# atxmega.net
KiCad netlist of a schematic drawn in Altium Designer
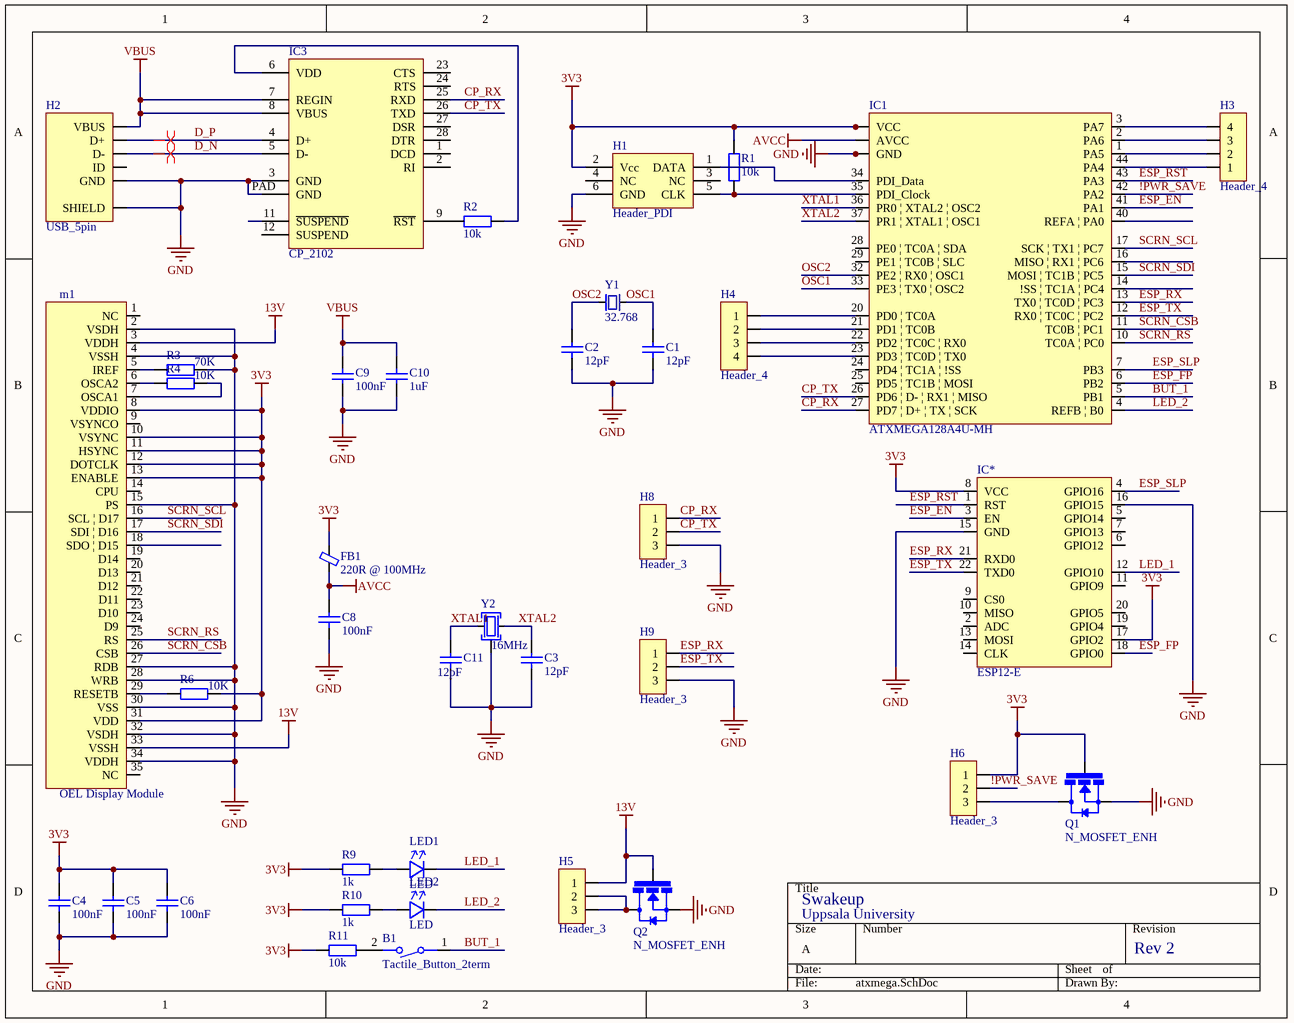
[diagram p0: atxmega.SchDoc]

(export (version "E")
  (design (tool "Eeschema 10.0.6"))
  (components
    (comp (ref "B1")
      (value "Tactile_Button_2term")
      (footprint "TACTILE_MINATUE_SMD_3.5x6mm")
      (libsource (lib "AranCustomFootprints") (part "Tactile_Button_2term"))
    )
    (comp (ref "C1")
      (value "12pF")
      (footprint "C0402")
      (description "Schematic symbol of a capacitor")
      (libsource (lib "AranCustomFootprints") (part "Capacitor"))
    )
    (comp (ref "C2")
      (value "12pF")
      (footprint "C0402")
      (description "Schematic symbol of a capacitor")
      (libsource (lib "AranCustomFootprints") (part "Capacitor"))
    )
    (comp (ref "C3")
      (value "12pF")
      (footprint "C0402")
      (description "Schematic symbol of a capacitor")
      (libsource (lib "AranCustomFootprints") (part "Capacitor"))
    )
    (comp (ref "C4")
      (value "100nF")
      (footprint "C0603")
      (description "Schematic symbol of a capacitor")
      (libsource (lib "AranCustomFootprints") (part "Capacitor"))
    )
    (comp (ref "C5")
      (value "100nF")
      (footprint "C0603")
      (description "Schematic symbol of a capacitor")
      (libsource (lib "AranCustomFootprints") (part "Capacitor"))
    )
    (comp (ref "C6")
      (value "100nF")
      (footprint "C0603")
      (description "Schematic symbol of a capacitor")
      (libsource (lib "AranCustomFootprints") (part "Capacitor"))
    )
    (comp (ref "C8")
      (value "100nF")
      (footprint "C0603")
      (description "Schematic symbol of a capacitor")
      (libsource (lib "AranCustomFootprints") (part "Capacitor"))
    )
    (comp (ref "C9")
      (value "100nF")
      (footprint "C0603")
      (description "Schematic symbol of a capacitor")
      (libsource (lib "AranCustomFootprints") (part "Capacitor"))
    )
    (comp (ref "C10")
      (value "1uF")
      (footprint "C0603")
      (description "Schematic symbol of a capacitor")
      (libsource (lib "AranCustomFootprints") (part "Capacitor"))
    )
    (comp (ref "C11")
      (value "12pF")
      (footprint "C0402")
      (description "Schematic symbol of a capacitor")
      (libsource (lib "AranCustomFootprints") (part "Capacitor"))
    )
    (comp (ref "FB1")
      (value "220R @ 100MHz")
      (footprint "L0805")
      (libsource (lib "AranCustomFootprints") (part "Ferrite"))
    )
    (comp (ref "H1")
      (value "Header_PDI")
      (footprint "6-HEADER_BOXED")
      (description "6-pin Boxed header with pinout used for PDI programming by Atmel programmers")
      (libsource (lib "AranCustomFootprints") (part "Header_PDI"))
    )
    (comp (ref "H2")
      (value "USB_5pin")
      (footprint "USB_Micro_B_RECEPTABLE_FCI")
      (description "5 Pins USB Connector")
      (libsource (lib "AranCustomFootprints") (part "USB_5pin"))
    )
    (comp (ref "H3")
      (value "Header_4")
      (footprint "Header_MALE_4")
      (description "Generic 4pin header symbol")
      (libsource (lib "AranCustomFootprints") (part "Header_4"))
    )
    (comp (ref "H4")
      (value "Header_4")
      (footprint "Header_MALE_4")
      (description "Generic 4pin header symbol")
      (libsource (lib "") (part "Header_4_1"))
    )
    (comp (ref "H5")
      (value "Header_3")
      (footprint "Header_MALE_3")
      (description "Generic 3pin header symbol")
      (libsource (lib "AranCustomFootprints") (part "Header_3"))
    )
    (comp (ref "H6")
      (value "Header_3")
      (footprint "Header_MALE_3")
      (description "Generic 3pin header symbol")
      (libsource (lib "AranCustomFootprints") (part "Header_3"))
    )
    (comp (ref "H8")
      (value "Header_3")
      (footprint "Header_MALE_3")
      (description "Generic 3pin header symbol")
      (libsource (lib "AranCustomFootprints") (part "Header_3"))
    )
    (comp (ref "H9")
      (value "Header_3")
      (footprint "Header_MALE_3")
      (description "Generic 3pin header symbol")
      (libsource (lib "AranCustomFootprints") (part "Header_3"))
    )
    (comp (ref "IC*") (value "ESP12-E") (footprint "ESP12-E") (libsource (lib "elmarlib") (part "ESP12-E")))
    (comp (ref "IC1")
      (value "ATXMEGA128A4U-MH")
      (footprint "44-VFQFN-E")
      (description "AVR AVR® XMEGA® A4U Microcontroller IC 8/16-Bit 32MHz 128KB (64K x 16) FLASH 44-VQFN (7x7)")
      (libsource (lib "elmarlib") (part "ATXMEGA128A4U-MH"))
    )
    (comp (ref "IC3")
      (value "CP_2102")
      (footprint "28-QFN_Exposed_pad")
      (description "Single chip USB to UART Bridge")
      (libsource (lib "AranCustomFootprints") (part "CP_2102"))
    )
    (comp (ref "LED1")
      (value "LED")
      (footprint "0603_LED")
      (description "Schematic symbol of a LED")
      (libsource (lib "AranCustomFootprints") (part "LED"))
    )
    (comp (ref "LED2")
      (value "LED")
      (footprint "0603_LED")
      (description "Schematic symbol of a LED")
      (libsource (lib "AranCustomFootprints") (part "LED"))
    )
    (comp (ref "m1")
      (value "OEL Display Module")
      (footprint "FFC-35-pin-0.5")
      (description "Part ID: UG-6028GDEAF01")
      (libsource (lib "elmarlib") (part "OEL Display Module"))
    )
    (comp (ref "Q1")
      (value "N_MOSFET_ENH")
      (footprint "SOT-23")
      (description "N Channel Enhancement type MOSFET schematic symbol")
      (libsource (lib "AranCustomFootprints") (part "N_MOSFET_ENH"))
    )
    (comp (ref "Q2")
      (value "N_MOSFET_ENH")
      (footprint "SOT-23")
      (description "N Channel Enhancement type MOSFET schematic symbol")
      (libsource (lib "AranCustomFootprints") (part "N_MOSFET_ENH"))
    )
    (comp (ref "R1")
      (value "10k")
      (footprint "R0603")
      (description "Schematic symbol of a resistor")
      (libsource (lib "AranCustomFootprints") (part "Resistor"))
    )
    (comp (ref "R2")
      (value "10k")
      (footprint "R0603")
      (description "Schematic symbol of a resistor")
      (libsource (lib "AranCustomFootprints") (part "Resistor"))
    )
    (comp (ref "R3")
      (value "70K")
      (footprint "R0603")
      (description "Schematic symbol of a resistor")
      (libsource (lib "AranCustomFootprints") (part "Resistor"))
    )
    (comp (ref "R4")
      (value "10K")
      (footprint "R0603")
      (description "Schematic symbol of a resistor")
      (libsource (lib "AranCustomFootprints") (part "Resistor"))
    )
    (comp (ref "R6")
      (value "10K")
      (footprint "R0603")
      (description "Schematic symbol of a resistor")
      (libsource (lib "AranCustomFootprints") (part "Resistor"))
    )
    (comp (ref "R9")
      (value "1k")
      (footprint "R0603")
      (description "Schematic symbol of a resistor")
      (libsource (lib "AranCustomFootprints") (part "Resistor"))
    )
    (comp (ref "R10")
      (value "1k")
      (footprint "R0603")
      (description "Schematic symbol of a resistor")
      (libsource (lib "AranCustomFootprints") (part "Resistor"))
    )
    (comp (ref "R11")
      (value "10k")
      (footprint "R0603")
      (description "Schematic symbol of a resistor")
      (libsource (lib "AranCustomFootprints") (part "Resistor"))
    )
    (comp (ref "Y1")
      (value "32.768")
      (footprint "crystal_6.2x2.1x2.1")
      (description "32.768kHz ±20ppm Crystal 12.5pF 35 kOhm -10°C ~ 60°C Through Hole Cylindrical Can, Radial")
      (libsource (lib "elmarlib") (part "Abracon LLC AB26T-32.768KHZ"))
    )
    (comp (ref "Y2")
      (value "16MHz")
      (footprint "Crystal_3.2x2.5")
      (description "Schematic symbol of a 2pin crystal with case connection")
      (libsource (lib "AranCustomFootprints") (part "Crystal_Ground"))
    )
  )
  (nets
    (net (code "1") (name "/!PWR_SAVE") (class "Default")
      (node (ref "H6") (pin "2") (pinfunction "2_2") (pintype "passive"))
      (node (ref "IC1") (pin "42") (pinfunction "PA2_42") (pintype "passive"))
    )
    (net (code "2") (name "/BUT_1") (class "Default")
      (node (ref "B1") (pin "1") (pintype "passive"))
      (node (ref "IC1") (pin "5") (pinfunction "PB1_5") (pintype "passive"))
    )
    (net (code "3") (name "/CP_RX") (class "Default")
      (node (ref "H8") (pin "1") (pinfunction "1_1") (pintype "passive"))
      (node (ref "IC1") (pin "27") (pinfunction "PD7_¦_D+_¦_TX_¦_SCK_27") (pintype "passive"))
      (node (ref "IC3") (pin "25") (pinfunction "RXD_25") (pintype "passive"))
    )
    (net (code "4") (name "/CP_TX") (class "Default")
      (node (ref "H8") (pin "2") (pinfunction "2_2") (pintype "passive"))
      (node (ref "IC1") (pin "26") (pinfunction "PD6_¦_D-_¦_RX1_¦_MISO_26") (pintype "passive"))
      (node (ref "IC3") (pin "26") (pinfunction "TXD_26") (pintype "passive"))
    )
    (net (code "5") (name "/D_N") (class "Default")
      (node (ref "H2") (pin "2") (pinfunction "D-_2") (pintype "passive"))
      (node (ref "IC3") (pin "5") (pinfunction "D-_5") (pintype "passive"))
    )
    (net (code "6") (name "/D_P") (class "Default")
      (node (ref "H2") (pin "3") (pinfunction "D+_3") (pintype "passive"))
      (node (ref "IC3") (pin "4") (pinfunction "D+_4") (pintype "passive"))
    )
    (net (code "7") (name "/ESP_EN") (class "Default")
      (node (ref "IC*") (pin "3") (pinfunction "EN_3") (pintype "passive"))
      (node (ref "IC1") (pin "41") (pinfunction "PA1_41") (pintype "passive"))
    )
    (net (code "8") (name "/ESP_FP") (class "Default")
      (node (ref "IC*") (pin "18") (pinfunction "GPIO0_18") (pintype "passive"))
      (node (ref "IC1") (pin "6") (pinfunction "PB2_6") (pintype "passive"))
    )
    (net (code "9") (name "/ESP_RST") (class "Default")
      (node (ref "IC*") (pin "1") (pinfunction "RST_1") (pintype "passive"))
      (node (ref "IC1") (pin "43") (pinfunction "PA3_43") (pintype "passive"))
    )
    (net (code "10") (name "/ESP_RX") (class "Default")
      (node (ref "H9") (pin "1") (pinfunction "1_1") (pintype "passive"))
      (node (ref "IC*") (pin "21") (pinfunction "RXD0_21") (pintype "passive"))
      (node (ref "IC1") (pin "13") (pinfunction "TX0_¦_TC0D_¦_PC3_13") (pintype "passive"))
    )
    (net (code "11") (name "/ESP_SLP") (class "Default")
      (node (ref "IC*") (pin "4") (pinfunction "GPIO16_4") (pintype "passive"))
      (node (ref "IC1") (pin "7") (pinfunction "PB3_7") (pintype "passive"))
    )
    (net (code "12") (name "/ESP_TX") (class "Default")
      (node (ref "H9") (pin "2") (pinfunction "2_2") (pintype "passive"))
      (node (ref "IC*") (pin "22") (pinfunction "TXD0_22") (pintype "passive"))
      (node (ref "IC1") (pin "12") (pinfunction "RX0_¦_TC0C_¦_PC2_12") (pintype "passive"))
    )
    (net (code "13") (name "/LED_1") (class "Default")
      (node (ref "IC*") (pin "12") (pinfunction "GPIO10_12") (pintype "passive"))
      (node (ref "LED1") (pin "C") (pinfunction "Cathode_C") (pintype "passive"))
    )
    (net (code "14") (name "/LED_2") (class "Default")
      (node (ref "IC1") (pin "4") (pinfunction "REFB_¦_B0_4") (pintype "passive"))
      (node (ref "LED2") (pin "C") (pinfunction "Cathode_C") (pintype "passive"))
    )
    (net (code "15") (name "/OSC1") (class "Default")
      (node (ref "C1") (pin "1") (pinfunction "1_1") (pintype "passive"))
      (node (ref "IC1") (pin "33") (pinfunction "PE3_¦_TX0_¦_OSC2_33") (pintype "passive"))
      (node (ref "Y1") (pin "0") (pinfunction "XTAL2_0") (pintype "passive"))
    )
    (net (code "16") (name "/OSC2") (class "Default")
      (node (ref "C2") (pin "1") (pinfunction "1_1") (pintype "passive"))
      (node (ref "IC1") (pin "32") (pinfunction "PE2_¦_RX0_¦_OSC1_32") (pintype "passive"))
      (node (ref "Y1") (pin "1") (pinfunction "XTAL1_1") (pintype "passive"))
    )
    (net (code "17") (name "/SCRN_CSB") (class "Default")
      (node (ref "IC1") (pin "11") (pinfunction "TC0B_¦_PC1_11") (pintype "passive"))
      (node (ref "m1") (pin "26") (pinfunction "CSB_26") (pintype "passive"))
    )
    (net (code "18") (name "/SCRN_RS") (class "Default")
      (node (ref "IC1") (pin "10") (pinfunction "TC0A_¦_PC0_10") (pintype "passive"))
      (node (ref "m1") (pin "25") (pinfunction "RS_25") (pintype "passive"))
    )
    (net (code "19") (name "/SCRN_SCL") (class "Default")
      (node (ref "IC1") (pin "17") (pinfunction "SCK_¦_TX1_¦_PC7_17") (pintype "passive"))
      (node (ref "m1") (pin "16") (pinfunction "SCL_¦_D17_16") (pintype "passive"))
    )
    (net (code "20") (name "/SCRN_SDI") (class "Default")
      (node (ref "IC1") (pin "15") (pinfunction "MOSI_¦_TC1B_¦_PC5_15") (pintype "passive"))
      (node (ref "m1") (pin "17") (pinfunction "SDI_¦_D16_17") (pintype "passive"))
    )
    (net (code "21") (name "/XTAL1") (class "Default")
      (node (ref "C11") (pin "1") (pinfunction "1_1") (pintype "passive"))
      (node (ref "IC1") (pin "36") (pinfunction "PR0_¦_XTAL2_¦_OSC2_36") (pintype "passive"))
      (node (ref "Y2") (pin "1") (pinfunction "1_1") (pintype "passive"))
    )
    (net (code "22") (name "/XTAL2") (class "Default")
      (node (ref "C3") (pin "1") (pinfunction "1_1") (pintype "passive"))
      (node (ref "IC1") (pin "37") (pinfunction "PR1_¦_XTAL1_¦_OSC1_37") (pintype "passive"))
      (node (ref "Y2") (pin "3") (pinfunction "3_3") (pintype "passive"))
    )
    (net (code "23") (name "3V3") (class "Default")
      (node (ref "C4") (pin "1") (pinfunction "1_1") (pintype "passive"))
      (node (ref "C5") (pin "1") (pinfunction "1_1") (pintype "passive"))
      (node (ref "C6") (pin "1") (pinfunction "1_1") (pintype "passive"))
      (node (ref "FB1") (pin "2") (pinfunction "2_2") (pintype "passive"))
      (node (ref "H1") (pin "2") (pinfunction "Vcc_2") (pintype "passive"))
      (node (ref "H6") (pin "1") (pinfunction "1_1") (pintype "passive"))
      (node (ref "IC*") (pin "17") (pinfunction "GPIO2_17") (pintype "passive"))
      (node (ref "IC*") (pin "8") (pinfunction "VCC_8") (pintype "passive"))
      (node (ref "IC1") (pin "19") (pinfunction "VCC_19") (pintype "passive"))
      (node (ref "IC1") (pin "31") (pinfunction "VCC_31") (pintype "passive"))
      (node (ref "IC1") (pin "9") (pinfunction "VCC_9") (pintype "passive"))
      (node (ref "Q1") (pin "1") (pinfunction "Gate_1") (pintype "passive"))
      (node (ref "R1") (pin "1") (pinfunction "1_1") (pintype "passive"))
      (node (ref "R10") (pin "1") (pinfunction "1_1") (pintype "passive"))
      (node (ref "R11") (pin "1") (pinfunction "1_1") (pintype "passive"))
      (node (ref "R6") (pin "1") (pinfunction "1_1") (pintype "passive"))
      (node (ref "R9") (pin "1") (pinfunction "1_1") (pintype "passive"))
      (node (ref "m1") (pin "10") (pinfunction "VSYNC_10") (pintype "passive"))
      (node (ref "m1") (pin "11") (pinfunction "HSYNC_11") (pintype "passive"))
      (node (ref "m1") (pin "12") (pinfunction "DOTCLK_12") (pintype "passive"))
      (node (ref "m1") (pin "13") (pinfunction "ENABLE_13") (pintype "passive"))
      (node (ref "m1") (pin "31") (pinfunction "VDD_31") (pintype "passive"))
      (node (ref "m1") (pin "8") (pinfunction "VDDIO_8") (pintype "passive"))
    )
    (net (code "24") (name "13V") (class "Default")
      (node (ref "H5") (pin "1") (pinfunction "1_1") (pintype "passive"))
      (node (ref "Q2") (pin "1") (pinfunction "Gate_1") (pintype "passive"))
      (node (ref "m1") (pin "3") (pinfunction "VDDH_3") (pintype "passive"))
      (node (ref "m1") (pin "33") (pinfunction "VSSH_33") (pintype "passive"))
    )
    (net (code "25") (name "AVCC") (class "Default")
      (node (ref "C8") (pin "1") (pinfunction "1_1") (pintype "passive"))
      (node (ref "FB1") (pin "1") (pinfunction "1_1") (pintype "passive"))
      (node (ref "IC1") (pin "39") (pinfunction "AVCC_39") (pintype "passive"))
    )
    (net (code "26") (name "GND") (class "Default")
      (node (ref "C1") (pin "2") (pinfunction "2_2") (pintype "passive"))
      (node (ref "C10") (pin "1") (pinfunction "1_1") (pintype "passive"))
      (node (ref "C11") (pin "2") (pinfunction "2_2") (pintype "passive"))
      (node (ref "C2") (pin "2") (pinfunction "2_2") (pintype "passive"))
      (node (ref "C3") (pin "2") (pinfunction "2_2") (pintype "passive"))
      (node (ref "C4") (pin "2") (pinfunction "2_2") (pintype "passive"))
      (node (ref "C5") (pin "2") (pinfunction "2_2") (pintype "passive"))
      (node (ref "C6") (pin "2") (pinfunction "2_2") (pintype "passive"))
      (node (ref "C8") (pin "2") (pinfunction "2_2") (pintype "passive"))
      (node (ref "C9") (pin "1") (pinfunction "1_1") (pintype "passive"))
      (node (ref "H1") (pin "6") (pinfunction "GND_6") (pintype "passive"))
      (node (ref "H2") (pin "5") (pinfunction "GND_5") (pintype "passive"))
      (node (ref "H2") (pin "SHIELD") (pinfunction "SHIELD_SHIELD") (pintype "passive"))
      (node (ref "H8") (pin "3") (pinfunction "3_3") (pintype "passive"))
      (node (ref "H9") (pin "3") (pinfunction "3_3") (pintype "passive"))
      (node (ref "IC*") (pin "15") (pinfunction "GND_15") (pintype "passive"))
      (node (ref "IC*") (pin "16") (pinfunction "GPIO15_16") (pintype "passive"))
      (node (ref "IC1") (pin "18") (pinfunction "GND_18") (pintype "passive"))
      (node (ref "IC1") (pin "30") (pinfunction "GND_30") (pintype "passive"))
      (node (ref "IC1") (pin "38") (pinfunction "GND_38") (pintype "passive"))
      (node (ref "IC1") (pin "45") (pinfunction "GND_45") (pintype "passive"))
      (node (ref "IC1") (pin "8") (pinfunction "GND_8") (pintype "passive"))
      (node (ref "IC3") (pin "3") (pinfunction "GND_3") (pintype "passive"))
      (node (ref "IC3") (pin "PAD") (pinfunction "GND_PAD") (pintype "passive"))
      (node (ref "Q1") (pin "2") (pinfunction "Source_2") (pintype "passive"))
      (node (ref "Q2") (pin "2") (pinfunction "Source_2") (pintype "passive"))
      (node (ref "R3") (pin "1") (pinfunction "1_1") (pintype "passive"))
      (node (ref "Y2") (pin "2") (pinfunction "2_2") (pintype "passive"))
      (node (ref "m1") (pin "15") (pinfunction "PS_15") (pintype "passive"))
      (node (ref "m1") (pin "2") (pinfunction "VSDH_2") (pintype "passive"))
      (node (ref "m1") (pin "27") (pinfunction "RDB_27") (pintype "passive"))
      (node (ref "m1") (pin "28") (pinfunction "WRB_28") (pintype "passive"))
      (node (ref "m1") (pin "30") (pinfunction "VSS_30") (pintype "passive"))
      (node (ref "m1") (pin "32") (pinfunction "VSDH_32") (pintype "passive"))
      (node (ref "m1") (pin "34") (pinfunction "VDDH_34") (pintype "passive"))
      (node (ref "m1") (pin "4") (pinfunction "VSSH_4") (pintype "passive"))
    )
    (net (code "27") (name "Net-(B1-Pad2)") (class "Default")
      (node (ref "B1") (pin "2") (pintype "passive"))
      (node (ref "R11") (pin "2") (pinfunction "2_2") (pintype "passive"))
    )
    (net (code "28") (name "Net-(H1-CLK)") (class "Default")
      (node (ref "H1") (pin "5") (pinfunction "CLK_5") (pintype "passive"))
      (node (ref "IC1") (pin "35") (pinfunction "PDI_Clock_35") (pintype "passive"))
      (node (ref "R1") (pin "2") (pinfunction "2_2") (pintype "passive"))
    )
    (net (code "29") (name "Net-(H1-DATA)") (class "Default")
      (node (ref "H1") (pin "1") (pinfunction "DATA_1") (pintype "passive"))
      (node (ref "IC1") (pin "34") (pinfunction "PDI_Data_34") (pintype "passive"))
    )
    (net (code "30") (name "Net-(IC1-PA4)") (class "Default")
      (node (ref "H3") (pin "1") (pinfunction "1_1") (pintype "passive"))
      (node (ref "IC1") (pin "44") (pinfunction "PA4_44") (pintype "passive"))
    )
    (net (code "31") (name "Net-(IC1-PA5)") (class "Default")
      (node (ref "H3") (pin "2") (pinfunction "2_2") (pintype "passive"))
      (node (ref "IC1") (pin "1") (pinfunction "PA5_1") (pintype "passive"))
    )
    (net (code "32") (name "Net-(IC1-PA6)") (class "Default")
      (node (ref "H3") (pin "3") (pinfunction "3_3") (pintype "passive"))
      (node (ref "IC1") (pin "2") (pinfunction "PA6_2") (pintype "passive"))
    )
    (net (code "33") (name "Net-(IC1-PA7)") (class "Default")
      (node (ref "H3") (pin "4") (pinfunction "4_4") (pintype "passive"))
      (node (ref "IC1") (pin "3") (pinfunction "PA7_3") (pintype "passive"))
    )
    (net (code "34") (name "Net-(IC1-PD0_¦_TC0A)") (class "Default")
      (node (ref "H4") (pin "1") (pinfunction "1_1") (pintype "passive"))
      (node (ref "IC1") (pin "20") (pinfunction "PD0_¦_TC0A_20") (pintype "passive"))
    )
    (net (code "35") (name "Net-(IC1-PD1_¦_TC0B)") (class "Default")
      (node (ref "H4") (pin "2") (pinfunction "2_2") (pintype "passive"))
      (node (ref "IC1") (pin "21") (pinfunction "PD1_¦_TC0B_21") (pintype "passive"))
    )
    (net (code "36") (name "Net-(IC1-PD2_¦_TC0C_¦_RX0)") (class "Default")
      (node (ref "H4") (pin "3") (pinfunction "3_3") (pintype "passive"))
      (node (ref "IC1") (pin "22") (pinfunction "PD2_¦_TC0C_¦_RX0_22") (pintype "passive"))
    )
    (net (code "37") (name "Net-(IC1-PD3_¦_TC0D_¦_TX0)") (class "Default")
      (node (ref "H4") (pin "4") (pinfunction "4_4") (pintype "passive"))
      (node (ref "IC1") (pin "23") (pinfunction "PD3_¦_TC0D_¦_TX0_23") (pintype "passive"))
    )
    (net (code "38") (name "Net-(IC3-VDD)") (class "Default")
      (node (ref "IC3") (pin "6") (pinfunction "VDD_6") (pintype "passive"))
      (node (ref "R2") (pin "1") (pinfunction "1_1") (pintype "passive"))
    )
    (net (code "39") (name "Net-(IC3-~{RST})") (class "Default")
      (node (ref "IC3") (pin "9") (pinfunction "~{RST}_9") (pintype "passive"))
      (node (ref "R2") (pin "2") (pinfunction "2_2") (pintype "passive"))
    )
    (net (code "40") (name "Net-(LED1-Anode)") (class "Default")
      (node (ref "LED1") (pin "A") (pinfunction "Anode_A") (pintype "passive"))
      (node (ref "R9") (pin "2") (pinfunction "2_2") (pintype "passive"))
    )
    (net (code "41") (name "Net-(LED2-Anode)") (class "Default")
      (node (ref "LED2") (pin "A") (pinfunction "Anode_A") (pintype "passive"))
      (node (ref "R10") (pin "2") (pinfunction "2_2") (pintype "passive"))
    )
    (net (code "42") (name "Net-(Q1-Drain)") (class "Default")
      (node (ref "H6") (pin "3") (pinfunction "3_3") (pintype "passive"))
      (node (ref "Q1") (pin "3") (pinfunction "Drain_3") (pintype "passive"))
    )
    (net (code "43") (name "Net-(Q2-Drain)") (class "Default")
      (node (ref "H5") (pin "2") (pinfunction "2_2") (pintype "passive"))
      (node (ref "H5") (pin "3") (pinfunction "3_3") (pintype "passive"))
      (node (ref "Q2") (pin "3") (pinfunction "Drain_3") (pintype "passive"))
    )
    (net (code "44") (name "Net-(m1-IREF)") (class "Default")
      (node (ref "R3") (pin "2") (pinfunction "2_2") (pintype "passive"))
      (node (ref "m1") (pin "5") (pinfunction "IREF_5") (pintype "passive"))
    )
    (net (code "45") (name "Net-(m1-OSCA1)") (class "Default")
      (node (ref "R4") (pin "1") (pinfunction "1_1") (pintype "passive"))
      (node (ref "m1") (pin "7") (pinfunction "OSCA1_7") (pintype "passive"))
    )
    (net (code "46") (name "Net-(m1-OSCA2)") (class "Default")
      (node (ref "R4") (pin "2") (pinfunction "2_2") (pintype "passive"))
      (node (ref "m1") (pin "6") (pinfunction "OSCA2_6") (pintype "passive"))
    )
    (net (code "47") (name "Net-(m1-RESETB)") (class "Default")
      (node (ref "R6") (pin "2") (pinfunction "2_2") (pintype "passive"))
      (node (ref "m1") (pin "29") (pinfunction "RESETB_29") (pintype "passive"))
    )
    (net (code "48") (name "VBUS") (class "Default")
      (node (ref "C10") (pin "2") (pinfunction "2_2") (pintype "passive"))
      (node (ref "C9") (pin "2") (pinfunction "2_2") (pintype "passive"))
      (node (ref "H2") (pin "1") (pinfunction "VBUS_1") (pintype "passive"))
      (node (ref "IC3") (pin "7") (pinfunction "REGIN_7") (pintype "passive"))
      (node (ref "IC3") (pin "8") (pinfunction "VBUS_8") (pintype "passive"))
    )
    (net (code "49") (name "unconnected-(H1-NC-Pad3)") (class "Default")
      (node (ref "H1") (pin "3") (pinfunction "NC_3") (pintype "passive"))
    )
    (net (code "50") (name "unconnected-(H1-NC-Pad4)") (class "Default")
      (node (ref "H1") (pin "4") (pinfunction "NC_4") (pintype "passive"))
    )
    (net (code "51") (name "unconnected-(H2-ID-Pad4)") (class "Default")
      (node (ref "H2") (pin "4") (pinfunction "ID_4") (pintype "passive"))
    )
    (net (code "52") (name "unconnected-(IC*-ADC-Pad2)") (class "Default")
      (node (ref "IC*") (pin "2") (pinfunction "ADC_2") (pintype "passive"))
    )
    (net (code "53") (name "unconnected-(IC*-CLK-Pad14)") (class "Default")
      (node (ref "IC*") (pin "14") (pinfunction "CLK_14") (pintype "passive"))
    )
    (net (code "54") (name "unconnected-(IC*-CS0-Pad9)") (class "Default")
      (node (ref "IC*") (pin "9") (pinfunction "CS0_9") (pintype "passive"))
    )
    (net (code "55") (name "unconnected-(IC*-GPIO4-Pad19)") (class "Default")
      (node (ref "IC*") (pin "19") (pinfunction "GPIO4_19") (pintype "passive"))
    )
    (net (code "56") (name "unconnected-(IC*-GPIO5-Pad20)") (class "Default")
      (node (ref "IC*") (pin "20") (pinfunction "GPIO5_20") (pintype "passive"))
    )
    (net (code "57") (name "unconnected-(IC*-GPIO9-Pad11)") (class "Default")
      (node (ref "IC*") (pin "11") (pinfunction "GPIO9_11") (pintype "passive"))
    )
    (net (code "58") (name "unconnected-(IC*-GPIO12-Pad6)") (class "Default")
      (node (ref "IC*") (pin "6") (pinfunction "GPIO12_6") (pintype "passive"))
    )
    (net (code "59") (name "unconnected-(IC*-GPIO13-Pad7)") (class "Default")
      (node (ref "IC*") (pin "7") (pinfunction "GPIO13_7") (pintype "passive"))
    )
    (net (code "60") (name "unconnected-(IC*-GPIO14-Pad5)") (class "Default")
      (node (ref "IC*") (pin "5") (pinfunction "GPIO14_5") (pintype "passive"))
    )
    (net (code "61") (name "unconnected-(IC*-MISO-Pad10)") (class "Default")
      (node (ref "IC*") (pin "10") (pinfunction "MISO_10") (pintype "passive"))
    )
    (net (code "62") (name "unconnected-(IC*-MOSI-Pad13)") (class "Default")
      (node (ref "IC*") (pin "13") (pinfunction "MOSI_13") (pintype "passive"))
    )
    (net (code "63") (name "unconnected-(IC1-!SS_¦_TC1A_¦_PC4-Pad14)") (class "Default")
      (node (ref "IC1") (pin "14") (pinfunction "!SS_¦_TC1A_¦_PC4_14") (pintype "passive"))
    )
    (net (code "64") (name "unconnected-(IC1-MISO_¦_RX1_¦_PC6-Pad16)") (class "Default")
      (node (ref "IC1") (pin "16") (pinfunction "MISO_¦_RX1_¦_PC6_16") (pintype "passive"))
    )
    (net (code "65") (name "unconnected-(IC1-PD4_¦_TC1A_¦_!SS-Pad24)") (class "Default")
      (node (ref "IC1") (pin "24") (pinfunction "PD4_¦_TC1A_¦_!SS_24") (pintype "passive"))
    )
    (net (code "66") (name "unconnected-(IC1-PD5_¦_TC1B_¦_MOSI-Pad25)") (class "Default")
      (node (ref "IC1") (pin "25") (pinfunction "PD5_¦_TC1B_¦_MOSI_25") (pintype "passive"))
    )
    (net (code "67") (name "unconnected-(IC1-PE0_¦_TC0A_¦_SDA-Pad28)") (class "Default")
      (node (ref "IC1") (pin "28") (pinfunction "PE0_¦_TC0A_¦_SDA_28") (pintype "passive"))
    )
    (net (code "68") (name "unconnected-(IC1-PE1_¦_TC0B_¦_SLC-Pad29)") (class "Default")
      (node (ref "IC1") (pin "29") (pinfunction "PE1_¦_TC0B_¦_SLC_29") (pintype "passive"))
    )
    (net (code "69") (name "unconnected-(IC1-REFA_¦_PA0-Pad40)") (class "Default")
      (node (ref "IC1") (pin "40") (pinfunction "REFA_¦_PA0_40") (pintype "passive"))
    )
    (net (code "70") (name "unconnected-(IC3-CTS-Pad23)") (class "Default")
      (node (ref "IC3") (pin "23") (pinfunction "CTS_23") (pintype "passive"))
    )
    (net (code "71") (name "unconnected-(IC3-DCD-Pad1)") (class "Default")
      (node (ref "IC3") (pin "1") (pinfunction "DCD_1") (pintype "passive"))
    )
    (net (code "72") (name "unconnected-(IC3-DSR-Pad27)") (class "Default")
      (node (ref "IC3") (pin "27") (pinfunction "DSR_27") (pintype "passive"))
    )
    (net (code "73") (name "unconnected-(IC3-DTR-Pad28)") (class "Default")
      (node (ref "IC3") (pin "28") (pinfunction "DTR_28") (pintype "passive"))
    )
    (net (code "74") (name "unconnected-(IC3-RI-Pad2)") (class "Default")
      (node (ref "IC3") (pin "2") (pinfunction "RI_2") (pintype "passive"))
    )
    (net (code "75") (name "unconnected-(IC3-RTS-Pad24)") (class "Default")
      (node (ref "IC3") (pin "24") (pinfunction "RTS_24") (pintype "passive"))
    )
    (net (code "76") (name "unconnected-(IC3-SUSPEND-Pad12)") (class "Default")
      (node (ref "IC3") (pin "12") (pinfunction "SUSPEND_12") (pintype "passive"))
    )
    (net (code "77") (name "unconnected-(IC3-~{SUSPEND}-Pad11)") (class "Default")
      (node (ref "IC3") (pin "11") (pinfunction "~{SUSPEND}_11") (pintype "passive"))
    )
    (net (code "78") (name "unconnected-(m1-CPU-Pad14)") (class "Default")
      (node (ref "m1") (pin "14") (pinfunction "CPU_14") (pintype "passive"))
    )
    (net (code "79") (name "unconnected-(m1-D9-Pad24)") (class "Default")
      (node (ref "m1") (pin "24") (pinfunction "D9_24") (pintype "passive"))
    )
    (net (code "80") (name "unconnected-(m1-D10-Pad23)") (class "Default")
      (node (ref "m1") (pin "23") (pinfunction "D10_23") (pintype "passive"))
    )
    (net (code "81") (name "unconnected-(m1-D11-Pad22)") (class "Default")
      (node (ref "m1") (pin "22") (pinfunction "D11_22") (pintype "passive"))
    )
    (net (code "82") (name "unconnected-(m1-D12-Pad21)") (class "Default")
      (node (ref "m1") (pin "21") (pinfunction "D12_21") (pintype "passive"))
    )
    (net (code "83") (name "unconnected-(m1-D13-Pad20)") (class "Default")
      (node (ref "m1") (pin "20") (pinfunction "D13_20") (pintype "passive"))
    )
    (net (code "84") (name "unconnected-(m1-D14-Pad19)") (class "Default")
      (node (ref "m1") (pin "19") (pinfunction "D14_19") (pintype "passive"))
    )
    (net (code "85") (name "unconnected-(m1-NC-Pad1)") (class "Default")
      (node (ref "m1") (pin "1") (pinfunction "NC_1") (pintype "passive"))
    )
    (net (code "86") (name "unconnected-(m1-NC-Pad35)") (class "Default")
      (node (ref "m1") (pin "35") (pinfunction "NC_35") (pintype "passive"))
    )
    (net (code "87") (name "unconnected-(m1-SDO_¦_D15-Pad18)") (class "Default")
      (node (ref "m1") (pin "18") (pinfunction "SDO_¦_D15_18") (pintype "passive"))
    )
    (net (code "88") (name "unconnected-(m1-VSYNCO-Pad9)") (class "Default")
      (node (ref "m1") (pin "9") (pinfunction "VSYNCO_9") (pintype "passive"))
    )
  )
)
